# BIT_5.net
KiCad netlist of a schematic drawn in EasyEDA
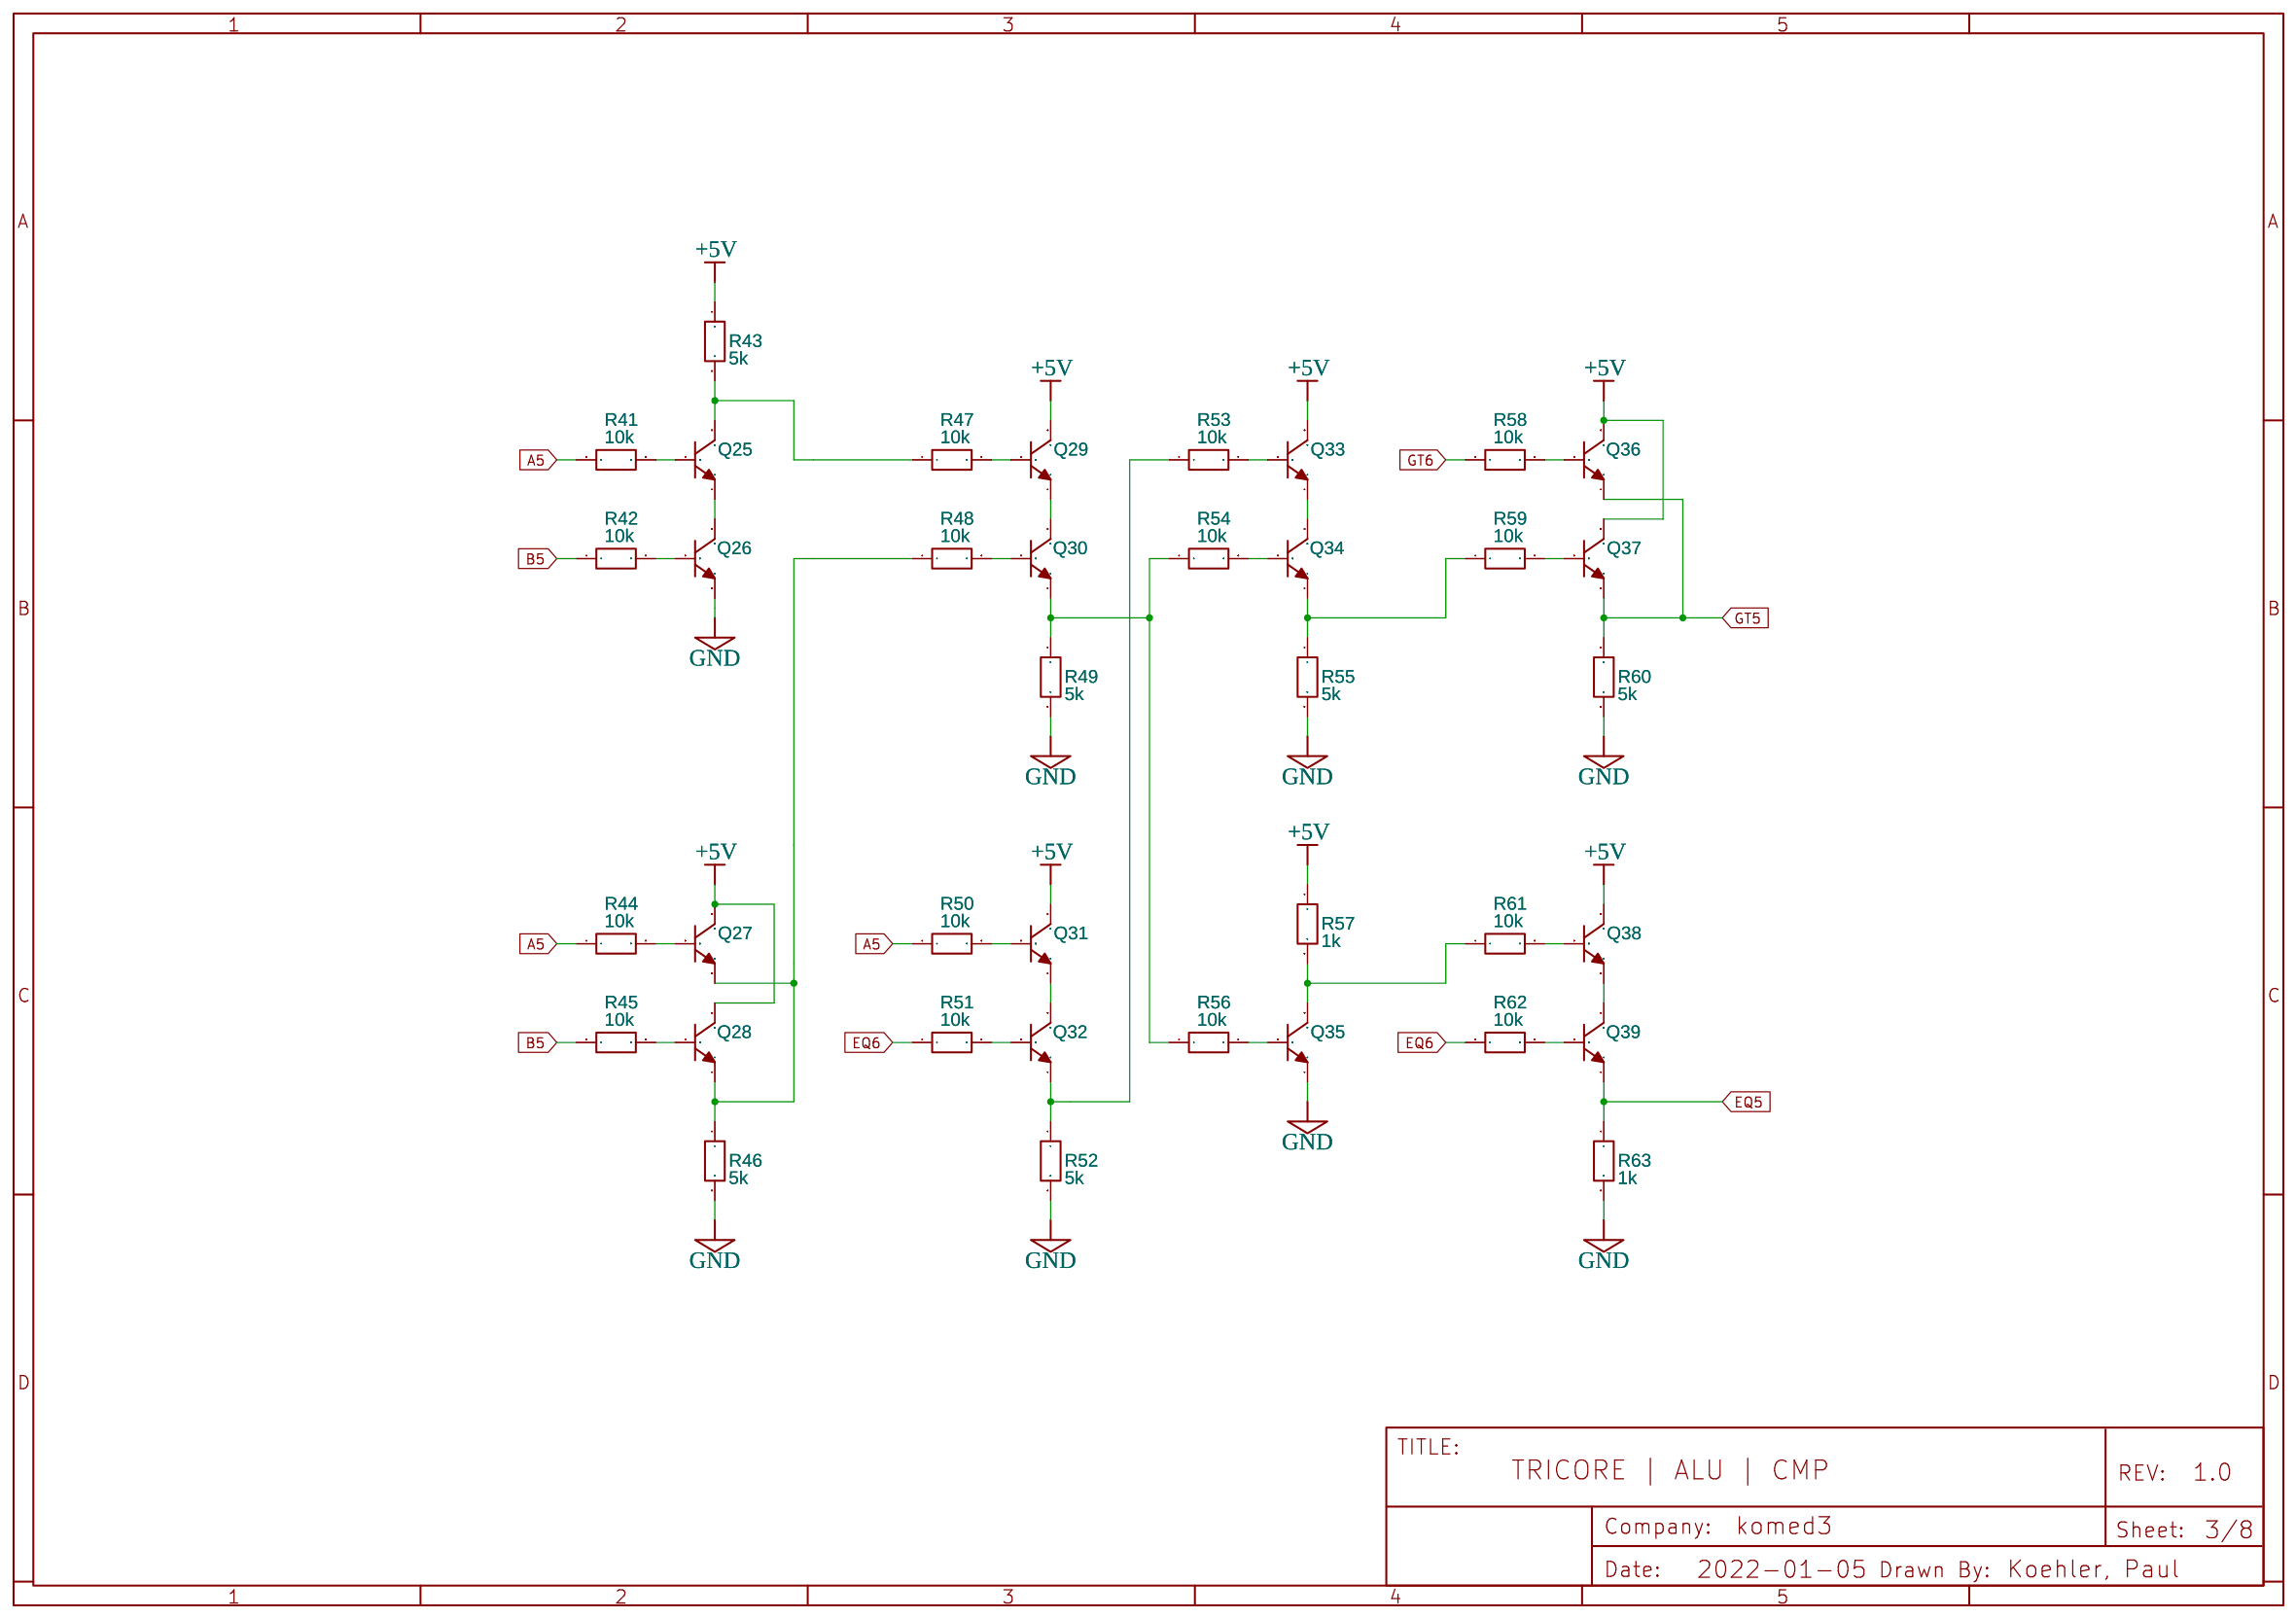
[diagram p0: schematic sheet]

(export (version "E")
  (design (tool "Eeschema 10.0.6"))
  (components
    (comp (ref "Q25")
      (value "2N3904(TO-92)")
      (fields (field (name "BOM_Manufacturer Part") "2N3904") (field (name "BOM_Supplier Part") "C118538"))
      (libsource (lib "") (part "2N3904(TO-92)"))
    )
    (comp (ref "Q26")
      (value "2N3904(TO-92)")
      (fields (field (name "BOM_Manufacturer Part") "2N3904") (field (name "BOM_Supplier Part") "C118538"))
      (libsource (lib "") (part "2N3904(TO-92)"))
    )
    (comp (ref "Q27")
      (value "2N3904(TO-92)")
      (fields (field (name "BOM_Manufacturer Part") "2N3904") (field (name "BOM_Supplier Part") "C118538"))
      (libsource (lib "") (part "2N3904(TO-92)"))
    )
    (comp (ref "Q28")
      (value "2N3904(TO-92)")
      (fields (field (name "BOM_Manufacturer Part") "2N3904") (field (name "BOM_Supplier Part") "C118538"))
      (libsource (lib "") (part "2N3904(TO-92)"))
    )
    (comp (ref "Q29")
      (value "2N3904(TO-92)")
      (fields (field (name "BOM_Manufacturer Part") "2N3904") (field (name "BOM_Supplier Part") "C118538"))
      (libsource (lib "") (part "2N3904(TO-92)"))
    )
    (comp (ref "Q30")
      (value "2N3904(TO-92)")
      (fields (field (name "BOM_Manufacturer Part") "2N3904") (field (name "BOM_Supplier Part") "C118538"))
      (libsource (lib "") (part "2N3904(TO-92)"))
    )
    (comp (ref "Q31")
      (value "2N3904(TO-92)")
      (fields (field (name "BOM_Manufacturer Part") "2N3904") (field (name "BOM_Supplier Part") "C118538"))
      (libsource (lib "") (part "2N3904(TO-92)"))
    )
    (comp (ref "Q32")
      (value "2N3904(TO-92)")
      (fields (field (name "BOM_Manufacturer Part") "2N3904") (field (name "BOM_Supplier Part") "C118538"))
      (libsource (lib "") (part "2N3904(TO-92)"))
    )
    (comp (ref "Q33")
      (value "2N3904(TO-92)")
      (fields (field (name "BOM_Manufacturer Part") "2N3904") (field (name "BOM_Supplier Part") "C118538"))
      (libsource (lib "") (part "2N3904(TO-92)"))
    )
    (comp (ref "Q34")
      (value "2N3904(TO-92)")
      (fields (field (name "BOM_Manufacturer Part") "2N3904") (field (name "BOM_Supplier Part") "C118538"))
      (libsource (lib "") (part "2N3904(TO-92)"))
    )
    (comp (ref "Q35")
      (value "2N3904(TO-92)")
      (fields (field (name "BOM_Manufacturer Part") "2N3904") (field (name "BOM_Supplier Part") "C118538"))
      (libsource (lib "") (part "2N3904(TO-92)"))
    )
    (comp (ref "Q36")
      (value "2N3904(TO-92)")
      (fields (field (name "BOM_Manufacturer Part") "2N3904") (field (name "BOM_Supplier Part") "C118538"))
      (libsource (lib "") (part "2N3904(TO-92)"))
    )
    (comp (ref "Q37")
      (value "2N3904(TO-92)")
      (fields (field (name "BOM_Manufacturer Part") "2N3904") (field (name "BOM_Supplier Part") "C118538"))
      (libsource (lib "") (part "2N3904(TO-92)"))
    )
    (comp (ref "Q38")
      (value "2N3904(TO-92)")
      (fields (field (name "BOM_Manufacturer Part") "2N3904") (field (name "BOM_Supplier Part") "C118538"))
      (libsource (lib "") (part "2N3904(TO-92)"))
    )
    (comp (ref "Q39")
      (value "2N3904(TO-92)")
      (fields (field (name "BOM_Manufacturer Part") "2N3904") (field (name "BOM_Supplier Part") "C118538"))
      (libsource (lib "") (part "2N3904(TO-92)"))
    )
    (comp (ref "R41") (value "10k") (libsource (lib "") (part "R_AXIAL-0.3_EU_1")))
    (comp (ref "R42") (value "10k") (libsource (lib "") (part "R_AXIAL-0.3_EU_1")))
    (comp (ref "R43") (value "5k") (libsource (lib "") (part "R_AXIAL-0.3_EU")))
    (comp (ref "R44") (value "10k") (libsource (lib "") (part "R_AXIAL-0.3_EU_1")))
    (comp (ref "R45") (value "10k") (libsource (lib "") (part "R_AXIAL-0.3_EU_1")))
    (comp (ref "R46") (value "5k") (libsource (lib "") (part "R_AXIAL-0.3_EU")))
    (comp (ref "R47") (value "10k") (libsource (lib "") (part "R_AXIAL-0.3_EU_1")))
    (comp (ref "R48") (value "10k") (libsource (lib "") (part "R_AXIAL-0.3_EU_1")))
    (comp (ref "R49") (value "5k") (libsource (lib "") (part "R_AXIAL-0.3_EU")))
    (comp (ref "R50") (value "10k") (libsource (lib "") (part "R_AXIAL-0.3_EU_1")))
    (comp (ref "R51") (value "10k") (libsource (lib "") (part "R_AXIAL-0.3_EU_1")))
    (comp (ref "R52") (value "5k") (libsource (lib "") (part "R_AXIAL-0.3_EU")))
    (comp (ref "R53") (value "10k") (libsource (lib "") (part "R_AXIAL-0.3_EU_1")))
    (comp (ref "R54") (value "10k") (libsource (lib "") (part "R_AXIAL-0.3_EU_1")))
    (comp (ref "R55") (value "5k") (libsource (lib "") (part "R_AXIAL-0.3_EU")))
    (comp (ref "R56") (value "10k") (libsource (lib "") (part "R_AXIAL-0.3_EU_1")))
    (comp (ref "R57") (value "1k") (libsource (lib "") (part "R_AXIAL-0.3_EU")))
    (comp (ref "R58") (value "10k") (libsource (lib "") (part "R_AXIAL-0.3_EU_1")))
    (comp (ref "R59") (value "10k") (libsource (lib "") (part "R_AXIAL-0.3_EU_1")))
    (comp (ref "R60") (value "5k") (libsource (lib "") (part "R_AXIAL-0.3_EU")))
    (comp (ref "R61") (value "10k") (libsource (lib "") (part "R_AXIAL-0.3_EU_1")))
    (comp (ref "R62") (value "10k") (libsource (lib "") (part "R_AXIAL-0.3_EU_1")))
    (comp (ref "R63") (value "1k") (libsource (lib "") (part "R_AXIAL-0.3_EU")))
  )
  (nets
    (net (code "1") (name "+5V") (class "Default")
      (node (ref "Q27") (pin "3") (pinfunction "C_3") (pintype "unspecified"))
      (node (ref "Q28") (pin "3") (pinfunction "C_3") (pintype "unspecified"))
      (node (ref "Q29") (pin "3") (pinfunction "C_3") (pintype "unspecified"))
      (node (ref "Q31") (pin "3") (pinfunction "C_3") (pintype "unspecified"))
      (node (ref "Q33") (pin "3") (pinfunction "C_3") (pintype "unspecified"))
      (node (ref "Q36") (pin "3") (pinfunction "C_3") (pintype "unspecified"))
      (node (ref "Q37") (pin "3") (pinfunction "C_3") (pintype "unspecified"))
      (node (ref "Q38") (pin "3") (pinfunction "C_3") (pintype "unspecified"))
      (node (ref "R43") (pin "1") (pinfunction "1_1") (pintype "unspecified"))
      (node (ref "R57") (pin "1") (pinfunction "1_1") (pintype "unspecified"))
    )
    (net (code "2") (name "A5") (class "Default")
      (node (ref "R41") (pin "1") (pinfunction "1_1") (pintype "unspecified"))
      (node (ref "R44") (pin "1") (pinfunction "1_1") (pintype "unspecified"))
      (node (ref "R50") (pin "1") (pinfunction "1_1") (pintype "unspecified"))
    )
    (net (code "3") (name "B5") (class "Default")
      (node (ref "R42") (pin "1") (pinfunction "1_1") (pintype "unspecified"))
      (node (ref "R45") (pin "1") (pinfunction "1_1") (pintype "unspecified"))
    )
    (net (code "4") (name "EQ5") (class "Default")
      (node (ref "Q39") (pin "1") (pinfunction "E_1") (pintype "unspecified"))
      (node (ref "R63") (pin "1") (pinfunction "1_1") (pintype "unspecified"))
    )
    (net (code "5") (name "EQ6") (class "Default")
      (node (ref "R51") (pin "1") (pinfunction "1_1") (pintype "unspecified"))
      (node (ref "R62") (pin "1") (pinfunction "1_1") (pintype "unspecified"))
    )
    (net (code "6") (name "GND") (class "Default")
      (node (ref "Q26") (pin "1") (pinfunction "E_1") (pintype "unspecified"))
      (node (ref "Q35") (pin "1") (pinfunction "E_1") (pintype "unspecified"))
      (node (ref "R46") (pin "2") (pinfunction "2_2") (pintype "unspecified"))
      (node (ref "R49") (pin "2") (pinfunction "2_2") (pintype "unspecified"))
      (node (ref "R52") (pin "2") (pinfunction "2_2") (pintype "unspecified"))
      (node (ref "R55") (pin "2") (pinfunction "2_2") (pintype "unspecified"))
      (node (ref "R60") (pin "2") (pinfunction "2_2") (pintype "unspecified"))
      (node (ref "R63") (pin "2") (pinfunction "2_2") (pintype "unspecified"))
    )
    (net (code "7") (name "GT5") (class "Default")
      (node (ref "Q36") (pin "1") (pinfunction "E_1") (pintype "unspecified"))
      (node (ref "Q37") (pin "1") (pinfunction "E_1") (pintype "unspecified"))
      (node (ref "R60") (pin "1") (pinfunction "1_1") (pintype "unspecified"))
    )
    (net (code "8") (name "GT6") (class "Default")
      (node (ref "R58") (pin "1") (pinfunction "1_1") (pintype "unspecified"))
    )
    (net (code "9") (name "Net-(Q25-B)") (class "Default")
      (node (ref "Q25") (pin "2") (pinfunction "B_2") (pintype "unspecified"))
      (node (ref "R41") (pin "2") (pinfunction "2_2") (pintype "unspecified"))
    )
    (net (code "10") (name "Net-(Q25-C)") (class "Default")
      (node (ref "Q25") (pin "3") (pinfunction "C_3") (pintype "unspecified"))
      (node (ref "R43") (pin "2") (pinfunction "2_2") (pintype "unspecified"))
      (node (ref "R47") (pin "1") (pinfunction "1_1") (pintype "unspecified"))
    )
    (net (code "11") (name "Net-(Q25-E)") (class "Default")
      (node (ref "Q25") (pin "1") (pinfunction "E_1") (pintype "unspecified"))
      (node (ref "Q26") (pin "3") (pinfunction "C_3") (pintype "unspecified"))
    )
    (net (code "12") (name "Net-(Q26-B)") (class "Default")
      (node (ref "Q26") (pin "2") (pinfunction "B_2") (pintype "unspecified"))
      (node (ref "R42") (pin "2") (pinfunction "2_2") (pintype "unspecified"))
    )
    (net (code "13") (name "Net-(Q27-B)") (class "Default")
      (node (ref "Q27") (pin "2") (pinfunction "B_2") (pintype "unspecified"))
      (node (ref "R44") (pin "2") (pinfunction "2_2") (pintype "unspecified"))
    )
    (net (code "14") (name "Net-(Q27-E)") (class "Default")
      (node (ref "Q27") (pin "1") (pinfunction "E_1") (pintype "unspecified"))
      (node (ref "Q28") (pin "1") (pinfunction "E_1") (pintype "unspecified"))
      (node (ref "R46") (pin "1") (pinfunction "1_1") (pintype "unspecified"))
      (node (ref "R48") (pin "1") (pinfunction "1_1") (pintype "unspecified"))
    )
    (net (code "15") (name "Net-(Q28-B)") (class "Default")
      (node (ref "Q28") (pin "2") (pinfunction "B_2") (pintype "unspecified"))
      (node (ref "R45") (pin "2") (pinfunction "2_2") (pintype "unspecified"))
    )
    (net (code "16") (name "Net-(Q29-B)") (class "Default")
      (node (ref "Q29") (pin "2") (pinfunction "B_2") (pintype "unspecified"))
      (node (ref "R47") (pin "2") (pinfunction "2_2") (pintype "unspecified"))
    )
    (net (code "17") (name "Net-(Q29-E)") (class "Default")
      (node (ref "Q29") (pin "1") (pinfunction "E_1") (pintype "unspecified"))
      (node (ref "Q30") (pin "3") (pinfunction "C_3") (pintype "unspecified"))
    )
    (net (code "18") (name "Net-(Q30-B)") (class "Default")
      (node (ref "Q30") (pin "2") (pinfunction "B_2") (pintype "unspecified"))
      (node (ref "R48") (pin "2") (pinfunction "2_2") (pintype "unspecified"))
    )
    (net (code "19") (name "Net-(Q30-E)") (class "Default")
      (node (ref "Q30") (pin "1") (pinfunction "E_1") (pintype "unspecified"))
      (node (ref "R49") (pin "1") (pinfunction "1_1") (pintype "unspecified"))
      (node (ref "R54") (pin "1") (pinfunction "1_1") (pintype "unspecified"))
      (node (ref "R56") (pin "1") (pinfunction "1_1") (pintype "unspecified"))
    )
    (net (code "20") (name "Net-(Q31-B)") (class "Default")
      (node (ref "Q31") (pin "2") (pinfunction "B_2") (pintype "unspecified"))
      (node (ref "R50") (pin "2") (pinfunction "2_2") (pintype "unspecified"))
    )
    (net (code "21") (name "Net-(Q31-E)") (class "Default")
      (node (ref "Q31") (pin "1") (pinfunction "E_1") (pintype "unspecified"))
      (node (ref "Q32") (pin "3") (pinfunction "C_3") (pintype "unspecified"))
    )
    (net (code "22") (name "Net-(Q32-B)") (class "Default")
      (node (ref "Q32") (pin "2") (pinfunction "B_2") (pintype "unspecified"))
      (node (ref "R51") (pin "2") (pinfunction "2_2") (pintype "unspecified"))
    )
    (net (code "23") (name "Net-(Q32-E)") (class "Default")
      (node (ref "Q32") (pin "1") (pinfunction "E_1") (pintype "unspecified"))
      (node (ref "R52") (pin "1") (pinfunction "1_1") (pintype "unspecified"))
      (node (ref "R53") (pin "1") (pinfunction "1_1") (pintype "unspecified"))
    )
    (net (code "24") (name "Net-(Q33-B)") (class "Default")
      (node (ref "Q33") (pin "2") (pinfunction "B_2") (pintype "unspecified"))
      (node (ref "R53") (pin "2") (pinfunction "2_2") (pintype "unspecified"))
    )
    (net (code "25") (name "Net-(Q33-E)") (class "Default")
      (node (ref "Q33") (pin "1") (pinfunction "E_1") (pintype "unspecified"))
      (node (ref "Q34") (pin "3") (pinfunction "C_3") (pintype "unspecified"))
    )
    (net (code "26") (name "Net-(Q34-B)") (class "Default")
      (node (ref "Q34") (pin "2") (pinfunction "B_2") (pintype "unspecified"))
      (node (ref "R54") (pin "2") (pinfunction "2_2") (pintype "unspecified"))
    )
    (net (code "27") (name "Net-(Q34-E)") (class "Default")
      (node (ref "Q34") (pin "1") (pinfunction "E_1") (pintype "unspecified"))
      (node (ref "R55") (pin "1") (pinfunction "1_1") (pintype "unspecified"))
      (node (ref "R59") (pin "1") (pinfunction "1_1") (pintype "unspecified"))
    )
    (net (code "28") (name "Net-(Q35-B)") (class "Default")
      (node (ref "Q35") (pin "2") (pinfunction "B_2") (pintype "unspecified"))
      (node (ref "R56") (pin "2") (pinfunction "2_2") (pintype "unspecified"))
    )
    (net (code "29") (name "Net-(Q35-C)") (class "Default")
      (node (ref "Q35") (pin "3") (pinfunction "C_3") (pintype "unspecified"))
      (node (ref "R57") (pin "2") (pinfunction "2_2") (pintype "unspecified"))
      (node (ref "R61") (pin "1") (pinfunction "1_1") (pintype "unspecified"))
    )
    (net (code "30") (name "Net-(Q36-B)") (class "Default")
      (node (ref "Q36") (pin "2") (pinfunction "B_2") (pintype "unspecified"))
      (node (ref "R58") (pin "2") (pinfunction "2_2") (pintype "unspecified"))
    )
    (net (code "31") (name "Net-(Q37-B)") (class "Default")
      (node (ref "Q37") (pin "2") (pinfunction "B_2") (pintype "unspecified"))
      (node (ref "R59") (pin "2") (pinfunction "2_2") (pintype "unspecified"))
    )
    (net (code "32") (name "Net-(Q38-B)") (class "Default")
      (node (ref "Q38") (pin "2") (pinfunction "B_2") (pintype "unspecified"))
      (node (ref "R61") (pin "2") (pinfunction "2_2") (pintype "unspecified"))
    )
    (net (code "33") (name "Net-(Q38-E)") (class "Default")
      (node (ref "Q38") (pin "1") (pinfunction "E_1") (pintype "unspecified"))
      (node (ref "Q39") (pin "3") (pinfunction "C_3") (pintype "unspecified"))
    )
    (net (code "34") (name "Net-(Q39-B)") (class "Default")
      (node (ref "Q39") (pin "2") (pinfunction "B_2") (pintype "unspecified"))
      (node (ref "R62") (pin "2") (pinfunction "2_2") (pintype "unspecified"))
    )
  )
)
